# ncv3020a-5v.net
KiCad netlist of a schematic drawn in EAGLE
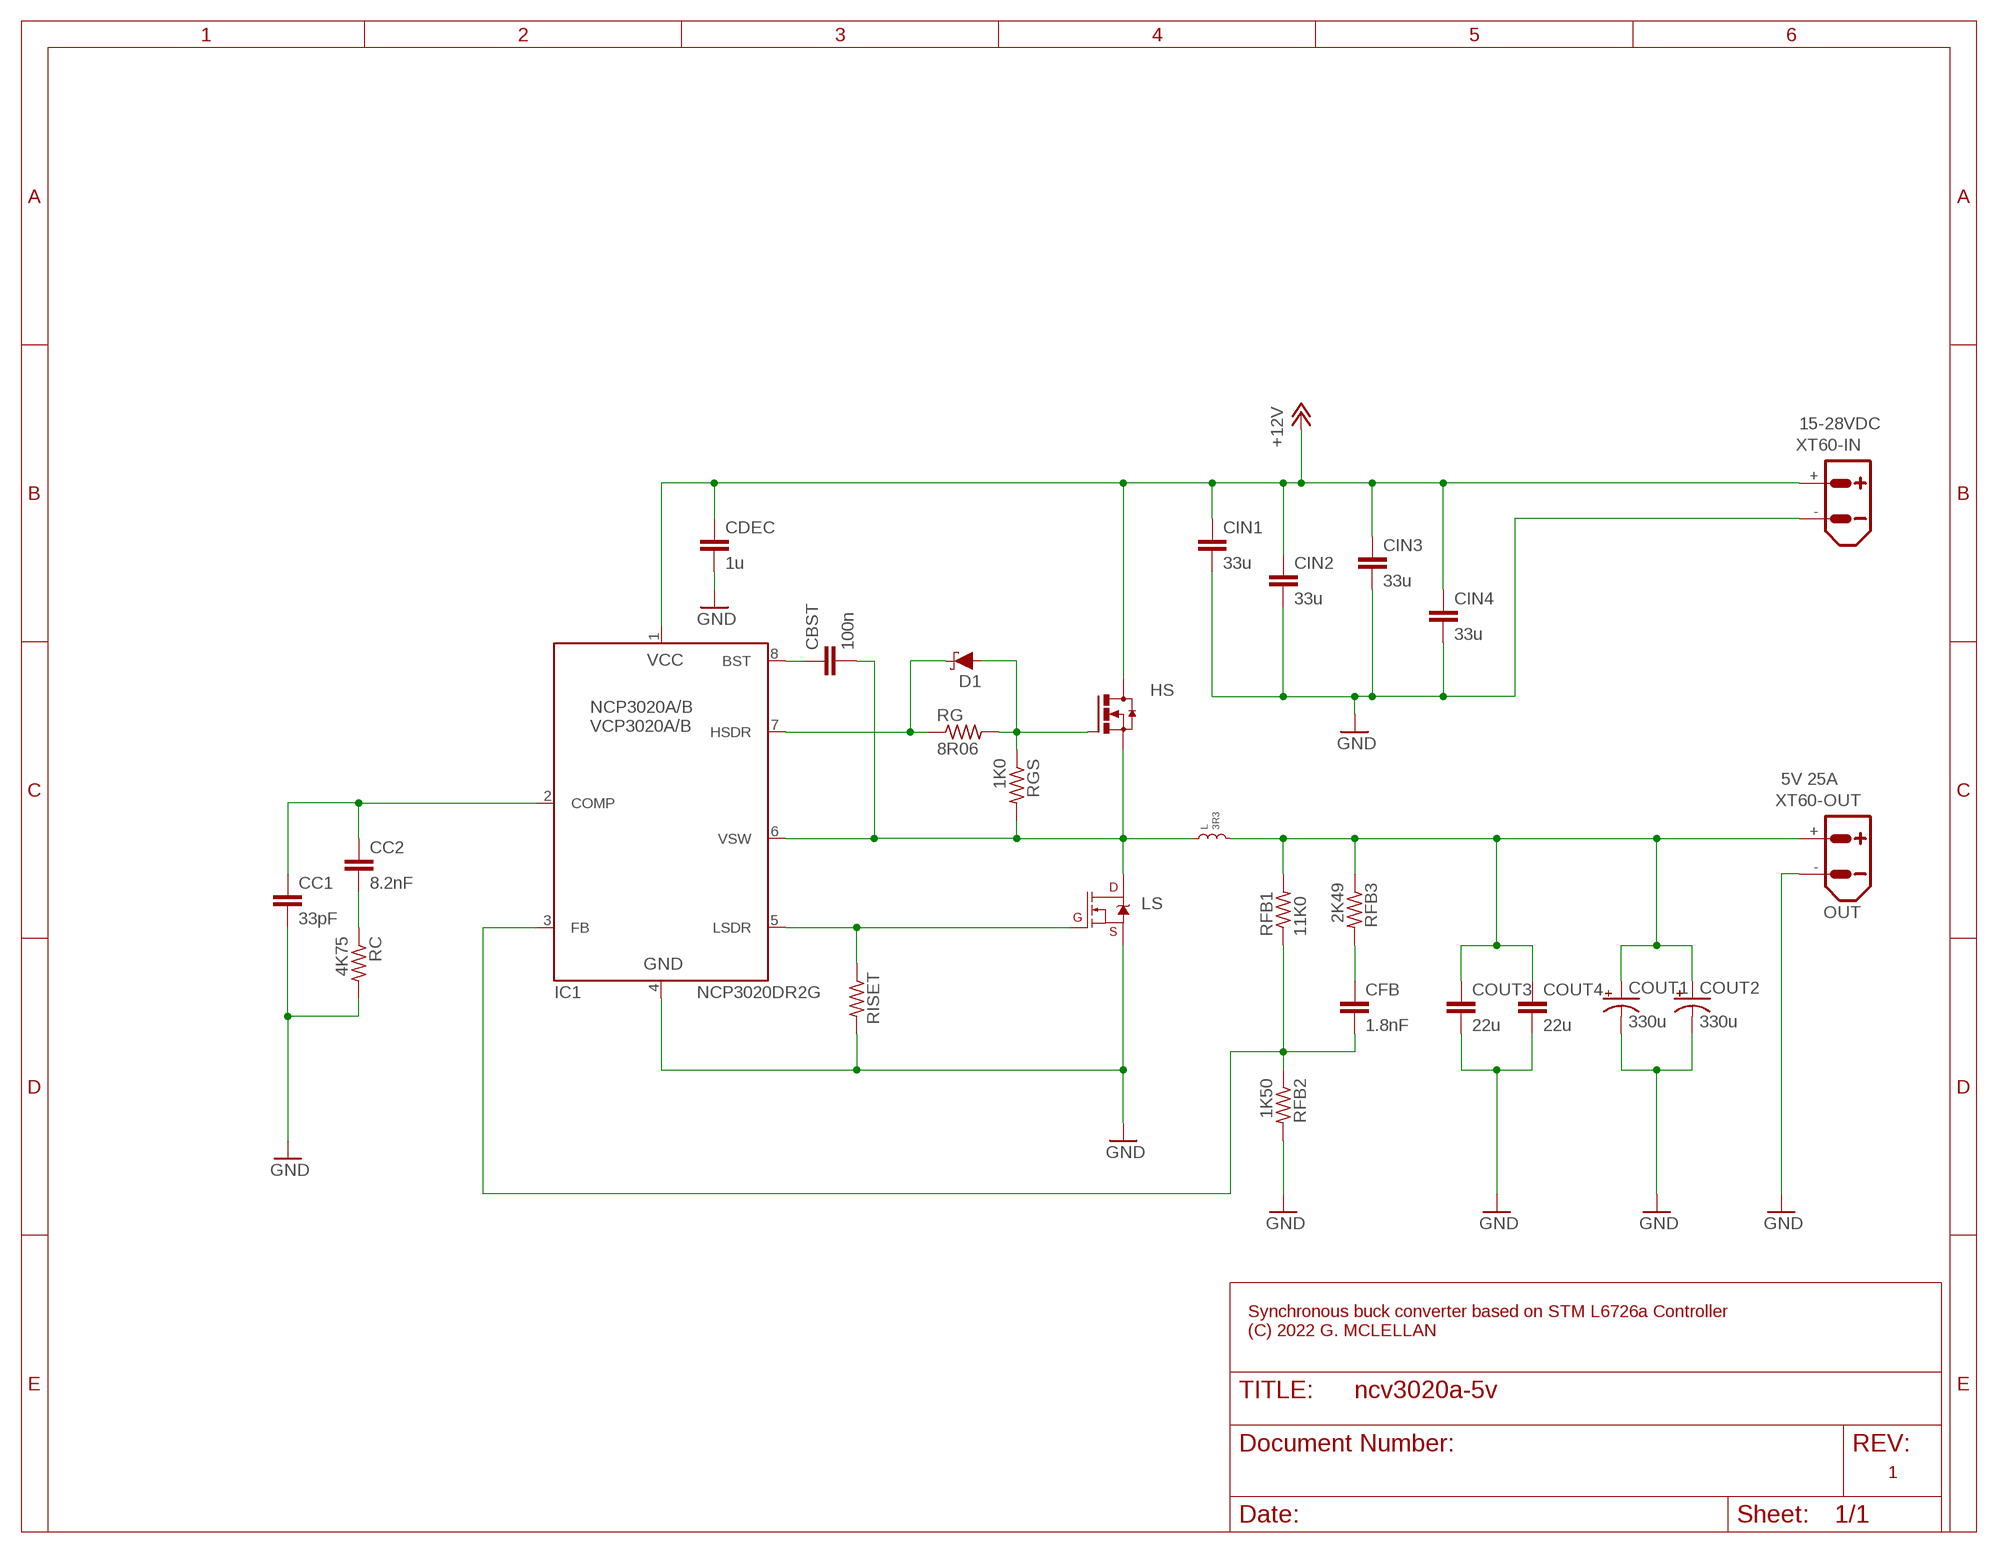
[diagram p0: schematic, sheet 1]

(export (version "E")
  (design (tool "Eeschema 10.0.6"))
  (components
    (comp (ref "CBST")
      (value "100n")
      (footprint "eagle-import:C0603")
      (libsource (lib "eagle-import") (part "C-EUC0603"))
    )
    (comp (ref "CC1")
      (value "33pF")
      (footprint "eagle-import:C0603")
      (libsource (lib "eagle-import") (part "C-EUC0603"))
    )
    (comp (ref "CC2")
      (value "8.2nF")
      (footprint "eagle-import:C0603")
      (libsource (lib "eagle-import") (part "C-EUC0603"))
    )
    (comp (ref "CDEC")
      (value "1u")
      (footprint "eagle-import:C1206")
      (libsource (lib "eagle-import") (part "C-EUC1206"))
    )
    (comp (ref "CFB")
      (value "1.8nF")
      (footprint "eagle-import:C0603")
      (libsource (lib "eagle-import") (part "C-EUC0603"))
    )
    (comp (ref "CIN1")
      (value "33u")
      (footprint "eagle-import:C2220K")
      (libsource (lib "eagle-import") (part "C-EUC2220K"))
    )
    (comp (ref "CIN2")
      (value "33u")
      (footprint "eagle-import:C2220K")
      (libsource (lib "eagle-import") (part "C-EUC2220K"))
    )
    (comp (ref "CIN3")
      (value "33u")
      (footprint "eagle-import:C2220K")
      (libsource (lib "eagle-import") (part "C-EUC2220K"))
    )
    (comp (ref "CIN4")
      (value "33u")
      (footprint "eagle-import:C2220K")
      (libsource (lib "eagle-import") (part "C-EUC2220K"))
    )
    (comp (ref "COUT1")
      (value "330u")
      (footprint "eagle-import:SANYO-OSCON_SMD_C6")
      (libsource (lib "eagle-import") (part "CPOL-USSANYO_SMD_C6"))
    )
    (comp (ref "COUT2")
      (value "330u")
      (footprint "eagle-import:SANYO-OSCON_SMD_C6")
      (libsource (lib "eagle-import") (part "CPOL-USSANYO_SMD_C6"))
    )
    (comp (ref "COUT3")
      (value "22u")
      (footprint "eagle-import:C1206")
      (libsource (lib "eagle-import") (part "C-EUC1206"))
    )
    (comp (ref "COUT4")
      (value "22u")
      (footprint "eagle-import:C1206")
      (libsource (lib "eagle-import") (part "C-EUC1206"))
    )
    (comp (ref "D1")
      (value "DIODE-SCHOTTKY-BAT20J")
      (footprint "eagle-import:SOD-323")
      (libsource (lib "eagle-import") (part "DIODE-SCHOTTKY-BAT20J"))
    )
    (comp (ref "HS")
      (value "N_MOSFET_POWERSO8")
      (footprint "eagle-import:POWERSO8")
      (libsource (lib "eagle-import") (part "N_MOSFET_POWERSO8"))
    )
    (comp (ref "IC1")
      (value "NCP3020DR2G")
      (footprint "eagle-import:SO-08")
      (libsource (lib "eagle-import") (part "NCP3020DR2G"))
    )
    (comp (ref "L")
      (value "3R3")
      (footprint "eagle-import:XAL1010")
      (libsource (lib "eagle-import") (part "INDUCTOR.XAL1010"))
    )
    (comp (ref "LS")
      (value "MOSFET-NCH-FDS6630A")
      (footprint "eagle-import:SO08")
      (libsource (lib "eagle-import") (part "MOSFET-NCH-FDS6630A"))
    )
    (comp (ref "RC")
      (value "4K75")
      (footprint "eagle-import:R0603")
      (libsource (lib "eagle-import") (part "R-US_R0603"))
    )
    (comp (ref "RFB1")
      (value "11K0")
      (footprint "eagle-import:R0805")
      (libsource (lib "eagle-import") (part "R-US_R0805"))
    )
    (comp (ref "RFB2")
      (value "1K50")
      (footprint "eagle-import:R0805")
      (libsource (lib "eagle-import") (part "R-US_R0805"))
    )
    (comp (ref "RFB3")
      (value "2K49")
      (footprint "eagle-import:R0805")
      (libsource (lib "eagle-import") (part "R-US_R0805"))
    )
    (comp (ref "RG")
      (value "8R06")
      (footprint "eagle-import:R0603")
      (libsource (lib "eagle-import") (part "R-US_R0603"))
    )
    (comp (ref "RGS")
      (value "1K0")
      (footprint "eagle-import:R0603")
      (libsource (lib "eagle-import") (part "R-US_R0603"))
    )
    (comp (ref "RISET")
      (value "R-US_R0603")
      (footprint "eagle-import:R0603")
      (libsource (lib "eagle-import") (part "R-US_R0603"))
    )
    (comp (ref "XT60-IN")
      (value "XT60PW-M")
      (footprint "eagle-import:XT60PW-M")
      (libsource (lib "eagle-import") (part "XT60PW-M"))
    )
    (comp (ref "XT60-OUT")
      (value "OUT")
      (footprint "eagle-import:XT60PW-M")
      (libsource (lib "eagle-import") (part "XT60PW-M"))
    )
  )
  (nets
    (net (code "1") (name "+12V") (class "Default")
      (node (ref "CDEC") (pin "1") (pinfunction "1_1") (pintype "passive"))
      (node (ref "CIN1") (pin "1") (pinfunction "1_1") (pintype "passive"))
      (node (ref "CIN2") (pin "1") (pinfunction "1_1") (pintype "passive"))
      (node (ref "CIN3") (pin "1") (pinfunction "1_1") (pintype "passive"))
      (node (ref "CIN4") (pin "1") (pinfunction "1_1") (pintype "passive"))
      (node (ref "HS") (pin "5") (pinfunction "D_5") (pintype "passive"))
      (node (ref "HS") (pin "6") (pinfunction "D_6") (pintype "passive"))
      (node (ref "HS") (pin "7") (pinfunction "D_7") (pintype "passive"))
      (node (ref "HS") (pin "8") (pinfunction "D_8") (pintype "passive"))
      (node (ref "HS") (pin "PAD") (pinfunction "D_PAD") (pintype "passive"))
      (node (ref "IC1") (pin "1") (pinfunction "VCC_1") (pintype "power_in"))
      (node (ref "XT60-IN") (pin "+") (pinfunction "+_+") (pintype "power_in"))
    )
    (net (code "2") (name "GND") (class "Default")
      (node (ref "CC1") (pin "2") (pinfunction "2_2") (pintype "passive"))
      (node (ref "CDEC") (pin "2") (pinfunction "2_2") (pintype "passive"))
      (node (ref "CIN1") (pin "2") (pinfunction "2_2") (pintype "passive"))
      (node (ref "CIN2") (pin "2") (pinfunction "2_2") (pintype "passive"))
      (node (ref "CIN3") (pin "2") (pinfunction "2_2") (pintype "passive"))
      (node (ref "CIN4") (pin "2") (pinfunction "2_2") (pintype "passive"))
      (node (ref "COUT1") (pin "-") (pinfunction "-_-") (pintype "passive"))
      (node (ref "COUT2") (pin "-") (pinfunction "-_-") (pintype "passive"))
      (node (ref "COUT3") (pin "2") (pinfunction "2_2") (pintype "passive"))
      (node (ref "COUT4") (pin "2") (pinfunction "2_2") (pintype "passive"))
      (node (ref "IC1") (pin "4") (pinfunction "GND_4") (pintype "power_in"))
      (node (ref "LS") (pin "1") (pinfunction "S_1") (pintype "bidirectional"))
      (node (ref "LS") (pin "2") (pinfunction "S_2") (pintype "bidirectional"))
      (node (ref "LS") (pin "3") (pinfunction "S_3") (pintype "bidirectional"))
      (node (ref "RC") (pin "2") (pinfunction "2_2") (pintype "passive"))
      (node (ref "RFB2") (pin "2") (pinfunction "2_2") (pintype "passive"))
      (node (ref "RISET") (pin "2") (pinfunction "2_2") (pintype "passive"))
      (node (ref "XT60-IN") (pin "-") (pinfunction "-_-") (pintype "power_in"))
      (node (ref "XT60-OUT") (pin "-") (pinfunction "-_-") (pintype "power_in"))
    )
    (net (code "3") (name "Net-(CC2-Pad2)") (class "Default")
      (node (ref "CC2") (pin "2") (pinfunction "2_2") (pintype "passive"))
      (node (ref "RC") (pin "1") (pinfunction "1_1") (pintype "passive"))
    )
    (net (code "4") (name "Net-(CFB-Pad1)") (class "Default")
      (node (ref "CFB") (pin "1") (pinfunction "1_1") (pintype "passive"))
      (node (ref "RFB3") (pin "2") (pinfunction "2_2") (pintype "passive"))
    )
    (net (code "5") (name "Net-(HS-G)") (class "Default")
      (node (ref "D1") (pin "A") (pinfunction "A_A") (pintype "passive"))
      (node (ref "HS") (pin "4") (pinfunction "G_4") (pintype "passive"))
      (node (ref "RG") (pin "2") (pinfunction "2_2") (pintype "passive"))
      (node (ref "RGS") (pin "1") (pinfunction "1_1") (pintype "passive"))
    )
    (net (code "6") (name "Net-(IC1-BST)") (class "Default")
      (node (ref "CBST") (pin "1") (pinfunction "1_1") (pintype "passive"))
      (node (ref "IC1") (pin "8") (pinfunction "BST_8") (pintype "power_in"))
    )
    (net (code "7") (name "Net-(IC1-COMP)") (class "Default")
      (node (ref "CC1") (pin "1") (pinfunction "1_1") (pintype "passive"))
      (node (ref "CC2") (pin "1") (pinfunction "1_1") (pintype "passive"))
      (node (ref "IC1") (pin "2") (pinfunction "COMP_2") (pintype "input"))
    )
    (net (code "8") (name "Net-(IC1-FB)") (class "Default")
      (node (ref "CFB") (pin "2") (pinfunction "2_2") (pintype "passive"))
      (node (ref "IC1") (pin "3") (pinfunction "FB_3") (pintype "input"))
      (node (ref "RFB1") (pin "1") (pinfunction "1_1") (pintype "passive"))
      (node (ref "RFB2") (pin "1") (pinfunction "1_1") (pintype "passive"))
    )
    (net (code "9") (name "Net-(IC1-HSDR)") (class "Default")
      (node (ref "D1") (pin "C") (pinfunction "C_C") (pintype "passive"))
      (node (ref "IC1") (pin "7") (pinfunction "HSDR_7") (pintype "output"))
      (node (ref "RG") (pin "1") (pinfunction "1_1") (pintype "passive"))
    )
    (net (code "10") (name "Net-(IC1-LSDR)") (class "Default")
      (node (ref "IC1") (pin "5") (pinfunction "LSDR_5") (pintype "output"))
      (node (ref "LS") (pin "4") (pinfunction "G_4") (pintype "bidirectional"))
      (node (ref "RISET") (pin "1") (pinfunction "1_1") (pintype "passive"))
    )
    (net (code "11") (name "Net-(IC1-VSW)") (class "Default")
      (node (ref "CBST") (pin "2") (pinfunction "2_2") (pintype "passive"))
      (node (ref "HS") (pin "1") (pinfunction "S_1") (pintype "passive"))
      (node (ref "HS") (pin "2") (pinfunction "S_2") (pintype "passive"))
      (node (ref "HS") (pin "3") (pinfunction "S_3") (pintype "passive"))
      (node (ref "IC1") (pin "6") (pinfunction "VSW_6") (pintype "input"))
      (node (ref "L") (pin "P$1") (pinfunction "1_P$1") (pintype "passive"))
      (node (ref "LS") (pin "5") (pinfunction "D_5") (pintype "bidirectional"))
      (node (ref "LS") (pin "6") (pinfunction "D_6") (pintype "bidirectional"))
      (node (ref "LS") (pin "7") (pinfunction "D_7") (pintype "bidirectional"))
      (node (ref "LS") (pin "8") (pinfunction "D_8") (pintype "bidirectional"))
      (node (ref "RGS") (pin "2") (pinfunction "2_2") (pintype "passive"))
    )
    (net (code "12") (name "Net-(L-2)") (class "Default")
      (node (ref "COUT1") (pin "+") (pinfunction "+_+") (pintype "passive"))
      (node (ref "COUT2") (pin "+") (pinfunction "+_+") (pintype "passive"))
      (node (ref "COUT3") (pin "1") (pinfunction "1_1") (pintype "passive"))
      (node (ref "COUT4") (pin "1") (pinfunction "1_1") (pintype "passive"))
      (node (ref "L") (pin "P$2") (pinfunction "2_P$2") (pintype "passive"))
      (node (ref "RFB1") (pin "2") (pinfunction "2_2") (pintype "passive"))
      (node (ref "RFB3") (pin "1") (pinfunction "1_1") (pintype "passive"))
      (node (ref "XT60-OUT") (pin "+") (pinfunction "+_+") (pintype "power_in"))
    )
  )
)
